# Sheet_1_2022-04-25.net
KiCad netlist of a schematic drawn in Altium Designer
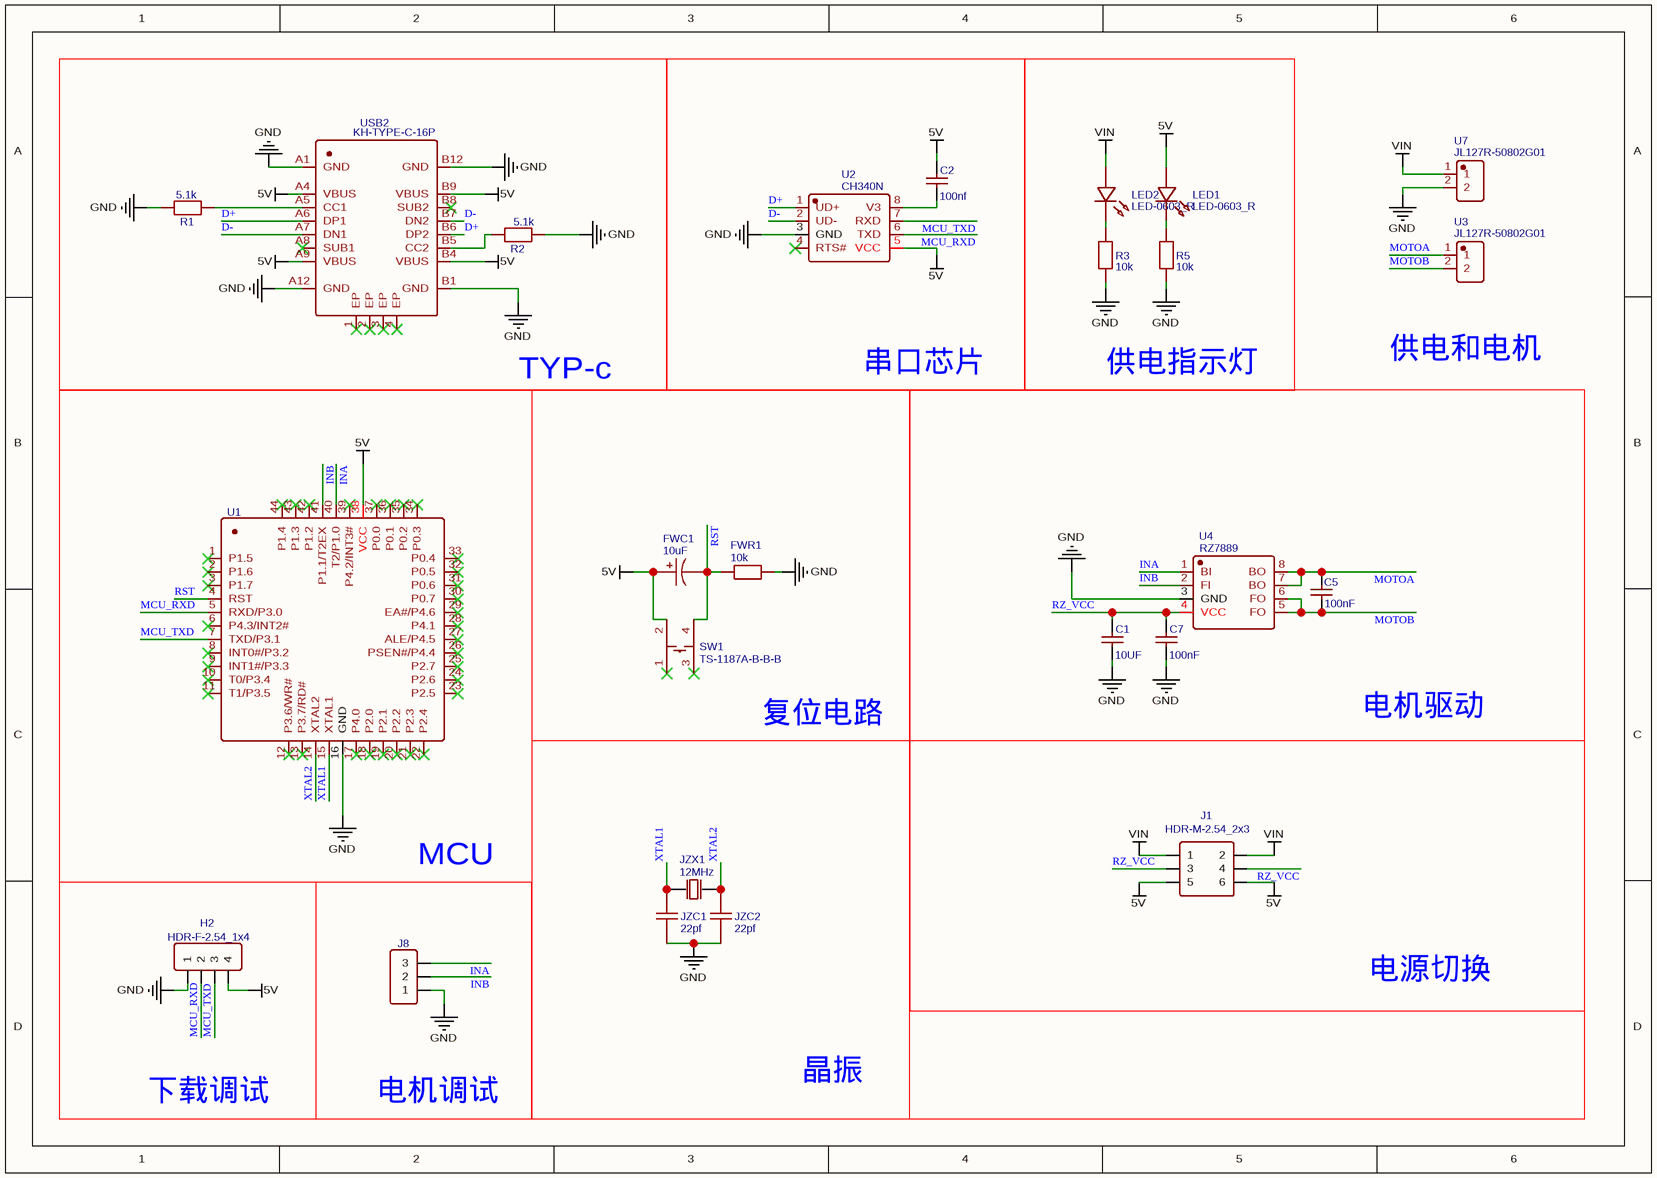
[diagram p0: Sheet_1_2022-04-25.schdoc]

(export (version "E")
  (design (tool "Eeschema 10.0.6"))
  (components
    (comp (ref "C1")
      (value "10UF")
      (fields
        (field (name "BOM_MANUFACTURER PART") "0603B104K500NT")
        (field (name "BOM_SUPPLIER PART") "C30926")
      )
      (libsource (lib "altium-import") (part "root_1_10UF_"))
    )
    (comp (ref "C2")
      (value "100nf")
      (fields
        (field (name "BOM_MANUFACTURER PART") "0603B104K500NT")
        (field (name "BOM_SUPPLIER PART") "C30926")
      )
      (libsource (lib "altium-import") (part "root_1_100nf_"))
    )
    (comp (ref "C5")
      (value "100nF")
      (fields
        (field (name "BOM_MANUFACTURER PART") "0603B104K500NT")
        (field (name "BOM_SUPPLIER PART") "C30926")
      )
      (libsource (lib "altium-import") (part "root_1_100nF_"))
    )
    (comp (ref "C7")
      (value "100nF")
      (fields
        (field (name "BOM_MANUFACTURER PART") "0603B104K500NT")
        (field (name "BOM_SUPPLIER PART") "C30926")
      )
      (libsource (lib "altium-import") (part "root_1_100nF_"))
    )
    (comp (ref "FWC1")
      (value "10uF")
      (fields (field (name "CONTRIBUTOR") "LCEDA_Lib"))
      (libsource (lib "altium-import") (part "root_0_10uF_"))
    )
    (comp (ref "FWR1")
      (value "10k")
      (fields (field (name "CONTRIBUTOR") "LCEDA_Lib"))
      (libsource (lib "altium-import") (part "root_2_10k_"))
    )
    (comp (ref "H2")
      (value "HDR-F-2.54_1x4")
      (fields (field (name "BOM_SUPPLIER PART") "C225501") (field (name "CONTRIBUTOR") "LCEDA_Lib"))
      (libsource (lib "altium-import") (part "root_1_HDR-F-2.54_1x4_"))
    )
    (comp (ref "J1")
      (value "HDR-M-2.54_2x3")
      (fields (field (name "BOM_SUPPLIER PART") "C65114") (field (name "CONTRIBUTOR") "LCEDA_Lib"))
      (libsource (lib "altium-import") (part "root_0_HDR-M-2.54_2x3_"))
    )
    (comp (ref "J8")
      (value "HDR-M-2.54_1x3")
      (fields (field (name "BOM_SUPPLIER PART") "C180248") (field (name "CONTRIBUTOR") "LCEDA_Lib"))
      (libsource (lib "altium-import") (part "root_2_HDR-M-2.54_1x3_"))
    )
    (comp (ref "JZC1")
      (value "22pf")
      (fields (field (name "CONTRIBUTOR") "LCEDA_Lib"))
      (libsource (lib "altium-import") (part "root_1_22pf_"))
    )
    (comp (ref "JZC2")
      (value "22pf")
      (fields (field (name "CONTRIBUTOR") "LCEDA_Lib"))
      (libsource (lib "altium-import") (part "root_1_22pf_"))
    )
    (comp (ref "JZX1")
      (value "12MHz")
      (fields
        (field (name "BOM_MANUFACTURER PART") "X49SD1431818MSD2SC")
        (field (name "BOM_SUPPLIER PART") "C2206")
      )
      (libsource (lib "altium-import") (part "root_2_12MHz_"))
    )
    (comp (ref "LED1")
      (value "LED-0603_R")
      (fields
        (field (name "BOM_MANUFACTURER PART") "19-217/R6C-AL1M2VY/3T")
        (field (name "BOM_SUPPLIER PART") "C72044")
        (field (name "CONTRIBUTOR") "LCEDA_01")
      )
      (libsource (lib "altium-import") (part "root_3_LED-0603_R_"))
    )
    (comp (ref "LED2")
      (value "LED-0603_R")
      (fields
        (field (name "BOM_MANUFACTURER PART") "19-217/R6C-AL1M2VY/3T")
        (field (name "BOM_SUPPLIER PART") "C72044")
        (field (name "CONTRIBUTOR") "LCEDA_01")
      )
      (libsource (lib "altium-import") (part "root_3_LED-0603_R_"))
    )
    (comp (ref "R1")
      (value "5.1k")
      (fields (field (name "CONTRIBUTOR") "LCEDA_Lib"))
      (libsource (lib "altium-import") (part "root_0_5.1k_"))
    )
    (comp (ref "R2")
      (value "5.1k")
      (fields (field (name "CONTRIBUTOR") "LCEDA_Lib"))
      (libsource (lib "altium-import") (part "root_0_5.1k_"))
    )
    (comp (ref "R3")
      (value "10k")
      (fields (field (name "CONTRIBUTOR") "LCEDA_Lib"))
      (libsource (lib "altium-import") (part "root_1_10k_"))
    )
    (comp (ref "R5")
      (value "10k")
      (fields (field (name "CONTRIBUTOR") "LCEDA_Lib"))
      (libsource (lib "altium-import") (part "root_1_10k_"))
    )
    (comp (ref "SW1")
      (value "TS-1187A-B-B-B")
      (fields (field (name "BOM_SUPPLIER PART") "C528026") (field (name "CONTRIBUTOR") "LCSC"))
      (libsource (lib "altium-import") (part "root_1_TS-1187A-B-B-B_"))
    )
    (comp (ref "U1")
      (value "C8707-40I_C8707")
      (fields
        (field (name "BOM_MANUFACTURER PART") "STC89C52RC-40I")
        (field (name "BOM_SUPPLIER PART") "C8707")
      )
      (libsource (lib "altium-import") (part "root_0_C8707-40I_C8707_"))
    )
    (comp (ref "U2")
      (value "CH340N")
      (fields (field (name "BOM_SUPPLIER PART") "C506813") (field (name "CONTRIBUTOR") "LCSC"))
      (libsource (lib "altium-import") (part "root_0_CH340N_"))
    )
    (comp (ref "U3")
      (value "JL127R-50802G01")
      (fields (field (name "BOM_SUPPLIER PART") "C2913255") (field (name "CONTRIBUTOR") "LCSC"))
      (libsource (lib "altium-import") (part "root_0_JL127R-50802G01_"))
    )
    (comp (ref "U4")
      (value "RZ7889")
      (fields (field (name "BOM_SUPPLIER PART") "C83668"))
      (libsource (lib "altium-import") (part "root_0_RZ7889_"))
    )
    (comp (ref "U7")
      (value "JL127R-50802G01")
      (fields (field (name "BOM_SUPPLIER PART") "C2913255") (field (name "CONTRIBUTOR") "LCSC"))
      (libsource (lib "altium-import") (part "root_0_JL127R-50802G01_"))
    )
    (comp (ref "USB2")
      (value "KH-TYPE-C-16P")
      (fields (field (name "BOM_SUPPLIER PART") "C709357") (field (name "CONTRIBUTOR") "LCSC"))
      (libsource (lib "altium-import") (part "root_0_KH-TYPE-C-16P_"))
    )
  )
  (nets
    (net (code "1") (name "/D+") (class "Default")
      (node (ref "U2") (pin "1") (pinfunction "UD+_1") (pintype "passive"))
      (node (ref "USB2") (pin "A6") (pinfunction "DP1_A6") (pintype "passive"))
      (node (ref "USB2") (pin "B6") (pinfunction "DP2_B6") (pintype "passive"))
    )
    (net (code "2") (name "/D-") (class "Default")
      (node (ref "U2") (pin "2") (pinfunction "UD-_2") (pintype "passive"))
      (node (ref "USB2") (pin "A7") (pinfunction "DN1_A7") (pintype "passive"))
      (node (ref "USB2") (pin "B7") (pinfunction "DN2_B7") (pintype "passive"))
    )
    (net (code "3") (name "/INA") (class "Default")
      (node (ref "J8") (pin "3") (pinfunction "3_3") (pintype "passive"))
      (node (ref "U1") (pin "40") (pinfunction "T2/P1.0_40") (pintype "passive"))
      (node (ref "U4") (pin "1") (pinfunction "BI_1") (pintype "passive"))
    )
    (net (code "4") (name "/INB") (class "Default")
      (node (ref "J8") (pin "2") (pinfunction "2_2") (pintype "passive"))
      (node (ref "U1") (pin "41") (pinfunction "P1.1/T2EX_41") (pintype "passive"))
      (node (ref "U4") (pin "2") (pinfunction "FI_2") (pintype "passive"))
    )
    (net (code "5") (name "/MCU_RXD") (class "Default")
      (node (ref "H2") (pin "2") (pinfunction "2_2") (pintype "passive"))
      (node (ref "U1") (pin "5") (pinfunction "RXD/P3.0_5") (pintype "passive"))
      (node (ref "U2") (pin "6") (pinfunction "TXD_6") (pintype "passive"))
    )
    (net (code "6") (name "/MCU_TXD") (class "Default")
      (node (ref "H2") (pin "3") (pinfunction "3_3") (pintype "passive"))
      (node (ref "U1") (pin "7") (pinfunction "TXD/P3.1_7") (pintype "passive"))
      (node (ref "U2") (pin "7") (pinfunction "RXD_7") (pintype "passive"))
    )
    (net (code "7") (name "/MOTOA") (class "Default")
      (node (ref "C5") (pin "2") (pinfunction "2_2") (pintype "passive"))
      (node (ref "U3") (pin "1") (pinfunction "1_1") (pintype "passive"))
      (node (ref "U4") (pin "7") (pinfunction "BO_7") (pintype "passive"))
      (node (ref "U4") (pin "8") (pinfunction "BO_8") (pintype "passive"))
    )
    (net (code "8") (name "/MOTOB") (class "Default")
      (node (ref "C5") (pin "1") (pinfunction "1_1") (pintype "passive"))
      (node (ref "U3") (pin "2") (pinfunction "2_2") (pintype "passive"))
      (node (ref "U4") (pin "5") (pinfunction "FO_5") (pintype "passive"))
      (node (ref "U4") (pin "6") (pinfunction "FO_6") (pintype "passive"))
    )
    (net (code "9") (name "/RST") (class "Default")
      (node (ref "FWC1") (pin "2") (pinfunction "2_2") (pintype "passive"))
      (node (ref "FWR1") (pin "2") (pinfunction "2_2") (pintype "passive"))
      (node (ref "SW1") (pin "4") (pinfunction "D_4") (pintype "passive"))
      (node (ref "U1") (pin "4") (pinfunction "RST_4") (pintype "passive"))
    )
    (net (code "10") (name "/RZ_VCC") (class "Default")
      (node (ref "C1") (pin "2") (pinfunction "2_2") (pintype "passive"))
      (node (ref "C7") (pin "2") (pinfunction "2_2") (pintype "passive"))
      (node (ref "J1") (pin "3") (pinfunction "3_3") (pintype "passive"))
      (node (ref "J1") (pin "4") (pinfunction "4_4") (pintype "passive"))
      (node (ref "U4") (pin "4") (pinfunction "VCC_4") (pintype "passive"))
    )
    (net (code "11") (name "/XTAL1") (class "Default")
      (node (ref "JZC1") (pin "2") (pinfunction "2_2") (pintype "passive"))
      (node (ref "JZX1") (pin "1") (pinfunction "OSC1_1") (pintype "passive"))
      (node (ref "U1") (pin "15") (pinfunction "XTAL1_15") (pintype "passive"))
    )
    (net (code "12") (name "/XTAL2") (class "Default")
      (node (ref "JZC2") (pin "2") (pinfunction "2_2") (pintype "passive"))
      (node (ref "JZX1") (pin "2") (pinfunction "OSC2_2") (pintype "passive"))
      (node (ref "U1") (pin "14") (pinfunction "XTAL2_14") (pintype "passive"))
    )
    (net (code "13") (name "5V") (class "Default")
      (node (ref "C2") (pin "2") (pinfunction "2_2") (pintype "passive"))
      (node (ref "FWC1") (pin "1") (pinfunction "1_1") (pintype "passive"))
      (node (ref "H2") (pin "4") (pinfunction "4_4") (pintype "passive"))
      (node (ref "J1") (pin "5") (pinfunction "5_5") (pintype "passive"))
      (node (ref "J1") (pin "6") (pinfunction "6_6") (pintype "passive"))
      (node (ref "LED1") (pin "1") (pinfunction "1_1") (pintype "passive"))
      (node (ref "SW1") (pin "2") (pinfunction "B_2") (pintype "passive"))
      (node (ref "U1") (pin "38") (pinfunction "VCC_38") (pintype "passive"))
      (node (ref "U2") (pin "5") (pinfunction "VCC_5") (pintype "passive"))
      (node (ref "USB2") (pin "A4") (pinfunction "VBUS_A4") (pintype "passive"))
      (node (ref "USB2") (pin "A9") (pinfunction "VBUS_A9") (pintype "passive"))
      (node (ref "USB2") (pin "B4") (pinfunction "VBUS_B4") (pintype "passive"))
      (node (ref "USB2") (pin "B9") (pinfunction "VBUS_B9") (pintype "passive"))
    )
    (net (code "14") (name "GND") (class "Default")
      (node (ref "C1") (pin "1") (pinfunction "1_1") (pintype "passive"))
      (node (ref "C7") (pin "1") (pinfunction "1_1") (pintype "passive"))
      (node (ref "FWR1") (pin "1") (pinfunction "1_1") (pintype "passive"))
      (node (ref "H2") (pin "1") (pinfunction "1_1") (pintype "passive"))
      (node (ref "J8") (pin "1") (pinfunction "1_1") (pintype "passive"))
      (node (ref "JZC1") (pin "1") (pinfunction "1_1") (pintype "passive"))
      (node (ref "JZC2") (pin "1") (pinfunction "1_1") (pintype "passive"))
      (node (ref "R1") (pin "1") (pinfunction "1_1") (pintype "passive"))
      (node (ref "R2") (pin "2") (pinfunction "2_2") (pintype "passive"))
      (node (ref "R3") (pin "1") (pinfunction "1_1") (pintype "passive"))
      (node (ref "R5") (pin "1") (pinfunction "1_1") (pintype "passive"))
      (node (ref "U1") (pin "16") (pinfunction "GND_16") (pintype "passive"))
      (node (ref "U2") (pin "3") (pinfunction "GND_3") (pintype "passive"))
      (node (ref "U4") (pin "3") (pinfunction "GND_3") (pintype "passive"))
      (node (ref "U7") (pin "2") (pinfunction "2_2") (pintype "passive"))
      (node (ref "USB2") (pin "A1") (pinfunction "GND_A1") (pintype "passive"))
      (node (ref "USB2") (pin "A12") (pinfunction "GND_A12") (pintype "passive"))
      (node (ref "USB2") (pin "B1") (pinfunction "GND_B1") (pintype "passive"))
      (node (ref "USB2") (pin "B12") (pinfunction "GND_B12") (pintype "passive"))
    )
    (net (code "15") (name "Net-(LED1-Pad2)") (class "Default")
      (node (ref "LED1") (pin "2") (pinfunction "2_2") (pintype "passive"))
      (node (ref "R5") (pin "2") (pinfunction "2_2") (pintype "passive"))
    )
    (net (code "16") (name "Net-(LED2-Pad2)") (class "Default")
      (node (ref "LED2") (pin "2") (pinfunction "2_2") (pintype "passive"))
      (node (ref "R3") (pin "2") (pinfunction "2_2") (pintype "passive"))
    )
    (net (code "17") (name "Net-(U2-V3)") (class "Default")
      (node (ref "C2") (pin "1") (pinfunction "1_1") (pintype "passive"))
      (node (ref "U2") (pin "8") (pinfunction "V3_8") (pintype "passive"))
    )
    (net (code "18") (name "Net-(USB2-CC1)") (class "Default")
      (node (ref "R1") (pin "2") (pinfunction "2_2") (pintype "passive"))
      (node (ref "USB2") (pin "A5") (pinfunction "CC1_A5") (pintype "passive"))
    )
    (net (code "19") (name "Net-(USB2-CC2)") (class "Default")
      (node (ref "R2") (pin "1") (pinfunction "1_1") (pintype "passive"))
      (node (ref "USB2") (pin "B5") (pinfunction "CC2_B5") (pintype "passive"))
    )
    (net (code "20") (name "VIN") (class "Default")
      (node (ref "J1") (pin "1") (pinfunction "1_1") (pintype "passive"))
      (node (ref "J1") (pin "2") (pinfunction "2_2") (pintype "passive"))
      (node (ref "LED2") (pin "1") (pinfunction "1_1") (pintype "passive"))
      (node (ref "U7") (pin "1") (pinfunction "1_1") (pintype "passive"))
    )
    (net (code "21") (name "unconnected-(SW1-A-Pad1)") (class "Default")
      (node (ref "SW1") (pin "1") (pinfunction "A_1") (pintype "passive+no_connect"))
    )
    (net (code "22") (name "unconnected-(SW1-C-Pad3)") (class "Default")
      (node (ref "SW1") (pin "3") (pinfunction "C_3") (pintype "passive+no_connect"))
    )
    (net (code "23") (name "unconnected-(U1-ALE{slash}P4.5-Pad27)") (class "Default")
      (node (ref "U1") (pin "27") (pinfunction "ALE/P4.5_27") (pintype "passive+no_connect"))
    )
    (net (code "24") (name "unconnected-(U1-EA#{slash}P4.6-Pad29)") (class "Default")
      (node (ref "U1") (pin "29") (pinfunction "EA#/P4.6_29") (pintype "passive+no_connect"))
    )
    (net (code "25") (name "unconnected-(U1-INT0#{slash}P3.2-Pad8)") (class "Default")
      (node (ref "U1") (pin "8") (pinfunction "INT0#/P3.2_8") (pintype "passive+no_connect"))
    )
    (net (code "26") (name "unconnected-(U1-INT1#{slash}P3.3-Pad9)") (class "Default")
      (node (ref "U1") (pin "9") (pinfunction "INT1#/P3.3_9") (pintype "passive+no_connect"))
    )
    (net (code "27") (name "unconnected-(U1-P0.0-Pad37)") (class "Default")
      (node (ref "U1") (pin "37") (pinfunction "P0.0_37") (pintype "passive+no_connect"))
    )
    (net (code "28") (name "unconnected-(U1-P0.1-Pad36)") (class "Default")
      (node (ref "U1") (pin "36") (pinfunction "P0.1_36") (pintype "passive+no_connect"))
    )
    (net (code "29") (name "unconnected-(U1-P0.2-Pad35)") (class "Default")
      (node (ref "U1") (pin "35") (pinfunction "P0.2_35") (pintype "passive+no_connect"))
    )
    (net (code "30") (name "unconnected-(U1-P0.3-Pad34)") (class "Default")
      (node (ref "U1") (pin "34") (pinfunction "P0.3_34") (pintype "passive+no_connect"))
    )
    (net (code "31") (name "unconnected-(U1-P0.4-Pad33)") (class "Default")
      (node (ref "U1") (pin "33") (pinfunction "P0.4_33") (pintype "passive+no_connect"))
    )
    (net (code "32") (name "unconnected-(U1-P0.5-Pad32)") (class "Default")
      (node (ref "U1") (pin "32") (pinfunction "P0.5_32") (pintype "passive+no_connect"))
    )
    (net (code "33") (name "unconnected-(U1-P0.6-Pad31)") (class "Default")
      (node (ref "U1") (pin "31") (pinfunction "P0.6_31") (pintype "passive+no_connect"))
    )
    (net (code "34") (name "unconnected-(U1-P0.7-Pad30)") (class "Default")
      (node (ref "U1") (pin "30") (pinfunction "P0.7_30") (pintype "passive+no_connect"))
    )
    (net (code "35") (name "unconnected-(U1-P1.2-Pad42)") (class "Default")
      (node (ref "U1") (pin "42") (pinfunction "P1.2_42") (pintype "passive+no_connect"))
    )
    (net (code "36") (name "unconnected-(U1-P1.3-Pad43)") (class "Default")
      (node (ref "U1") (pin "43") (pinfunction "P1.3_43") (pintype "passive+no_connect"))
    )
    (net (code "37") (name "unconnected-(U1-P1.4-Pad44)") (class "Default")
      (node (ref "U1") (pin "44") (pinfunction "P1.4_44") (pintype "passive+no_connect"))
    )
    (net (code "38") (name "unconnected-(U1-P1.5-Pad1)") (class "Default")
      (node (ref "U1") (pin "1") (pinfunction "P1.5_1") (pintype "passive+no_connect"))
    )
    (net (code "39") (name "unconnected-(U1-P1.6-Pad2)") (class "Default")
      (node (ref "U1") (pin "2") (pinfunction "P1.6_2") (pintype "passive+no_connect"))
    )
    (net (code "40") (name "unconnected-(U1-P1.7-Pad3)") (class "Default")
      (node (ref "U1") (pin "3") (pinfunction "P1.7_3") (pintype "passive+no_connect"))
    )
    (net (code "41") (name "unconnected-(U1-P2.0-Pad18)") (class "Default")
      (node (ref "U1") (pin "18") (pinfunction "P2.0_18") (pintype "passive+no_connect"))
    )
    (net (code "42") (name "unconnected-(U1-P2.1-Pad19)") (class "Default")
      (node (ref "U1") (pin "19") (pinfunction "P2.1_19") (pintype "passive+no_connect"))
    )
    (net (code "43") (name "unconnected-(U1-P2.2-Pad20)") (class "Default")
      (node (ref "U1") (pin "20") (pinfunction "P2.2_20") (pintype "passive+no_connect"))
    )
    (net (code "44") (name "unconnected-(U1-P2.3-Pad21)") (class "Default")
      (node (ref "U1") (pin "21") (pinfunction "P2.3_21") (pintype "passive+no_connect"))
    )
    (net (code "45") (name "unconnected-(U1-P2.4-Pad22)") (class "Default")
      (node (ref "U1") (pin "22") (pinfunction "P2.4_22") (pintype "passive+no_connect"))
    )
    (net (code "46") (name "unconnected-(U1-P2.5-Pad23)") (class "Default")
      (node (ref "U1") (pin "23") (pinfunction "P2.5_23") (pintype "passive+no_connect"))
    )
    (net (code "47") (name "unconnected-(U1-P2.6-Pad24)") (class "Default")
      (node (ref "U1") (pin "24") (pinfunction "P2.6_24") (pintype "passive+no_connect"))
    )
    (net (code "48") (name "unconnected-(U1-P2.7-Pad25)") (class "Default")
      (node (ref "U1") (pin "25") (pinfunction "P2.7_25") (pintype "passive+no_connect"))
    )
    (net (code "49") (name "unconnected-(U1-P3.6{slash}WR#-Pad12)") (class "Default")
      (node (ref "U1") (pin "12") (pinfunction "P3.6/WR#_12") (pintype "passive+no_connect"))
    )
    (net (code "50") (name "unconnected-(U1-P3.7{slash}RD#-Pad13)") (class "Default")
      (node (ref "U1") (pin "13") (pinfunction "P3.7/RD#_13") (pintype "passive+no_connect"))
    )
    (net (code "51") (name "unconnected-(U1-P4.0-Pad17)") (class "Default")
      (node (ref "U1") (pin "17") (pinfunction "P4.0_17") (pintype "passive+no_connect"))
    )
    (net (code "52") (name "unconnected-(U1-P4.1-Pad28)") (class "Default")
      (node (ref "U1") (pin "28") (pinfunction "P4.1_28") (pintype "passive+no_connect"))
    )
    (net (code "53") (name "unconnected-(U1-P4.2{slash}INT3#-Pad39)") (class "Default")
      (node (ref "U1") (pin "39") (pinfunction "P4.2/INT3#_39") (pintype "passive+no_connect"))
    )
    (net (code "54") (name "unconnected-(U1-P4.3{slash}INT2#-Pad6)") (class "Default")
      (node (ref "U1") (pin "6") (pinfunction "P4.3/INT2#_6") (pintype "passive+no_connect"))
    )
    (net (code "55") (name "unconnected-(U1-PSEN#{slash}P4.4-Pad26)") (class "Default")
      (node (ref "U1") (pin "26") (pinfunction "PSEN#/P4.4_26") (pintype "passive+no_connect"))
    )
    (net (code "56") (name "unconnected-(U1-T0{slash}P3.4-Pad10)") (class "Default")
      (node (ref "U1") (pin "10") (pinfunction "T0/P3.4_10") (pintype "passive+no_connect"))
    )
    (net (code "57") (name "unconnected-(U1-T1{slash}P3.5-Pad11)") (class "Default")
      (node (ref "U1") (pin "11") (pinfunction "T1/P3.5_11") (pintype "passive+no_connect"))
    )
    (net (code "58") (name "unconnected-(U2-RTS#-Pad4)") (class "Default")
      (node (ref "U2") (pin "4") (pinfunction "RTS#_4") (pintype "passive+no_connect"))
    )
    (net (code "59") (name "unconnected-(USB2-EP-Pad1)") (class "Default")
      (node (ref "USB2") (pin "1") (pinfunction "EP_1") (pintype "passive+no_connect"))
    )
    (net (code "60") (name "unconnected-(USB2-EP-Pad2)") (class "Default")
      (node (ref "USB2") (pin "2") (pinfunction "EP_2") (pintype "passive+no_connect"))
    )
    (net (code "61") (name "unconnected-(USB2-EP-Pad3)") (class "Default")
      (node (ref "USB2") (pin "3") (pinfunction "EP_3") (pintype "passive+no_connect"))
    )
    (net (code "62") (name "unconnected-(USB2-EP-Pad4)") (class "Default")
      (node (ref "USB2") (pin "4") (pinfunction "EP_4") (pintype "passive+no_connect"))
    )
    (net (code "63") (name "unconnected-(USB2-SUB1-PadA8)") (class "Default")
      (node (ref "USB2") (pin "A8") (pinfunction "SUB1_A8") (pintype "passive+no_connect"))
    )
    (net (code "64") (name "unconnected-(USB2-SUB2-PadB8)") (class "Default")
      (node (ref "USB2") (pin "B8") (pinfunction "SUB2_B8") (pintype "passive+no_connect"))
    )
  )
)
